# DIDV_-_Controle_Corrente_Total.net
KiCad netlist of a schematic drawn in EAGLE
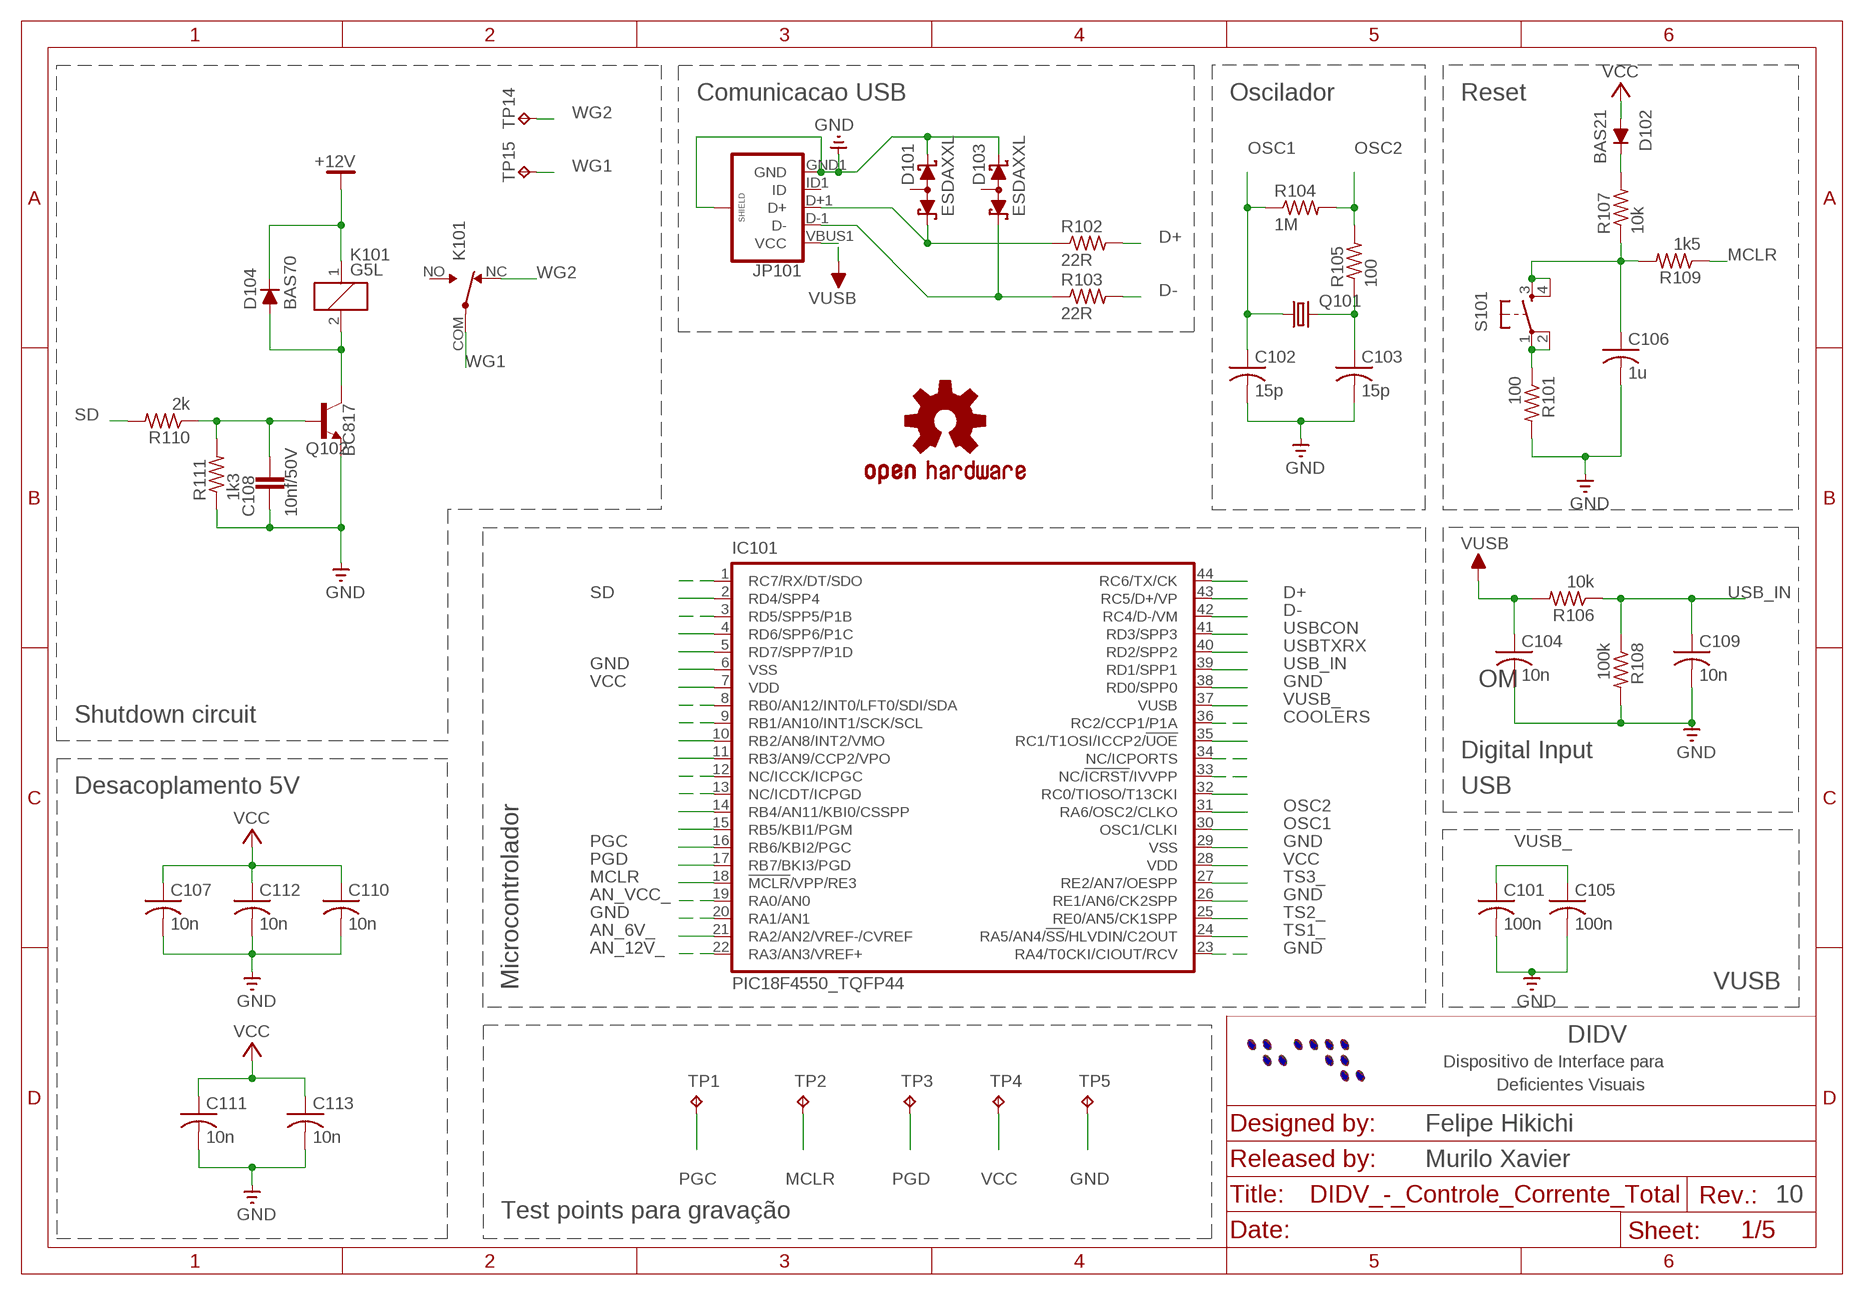
[diagram p0: schematic, sheet 1]
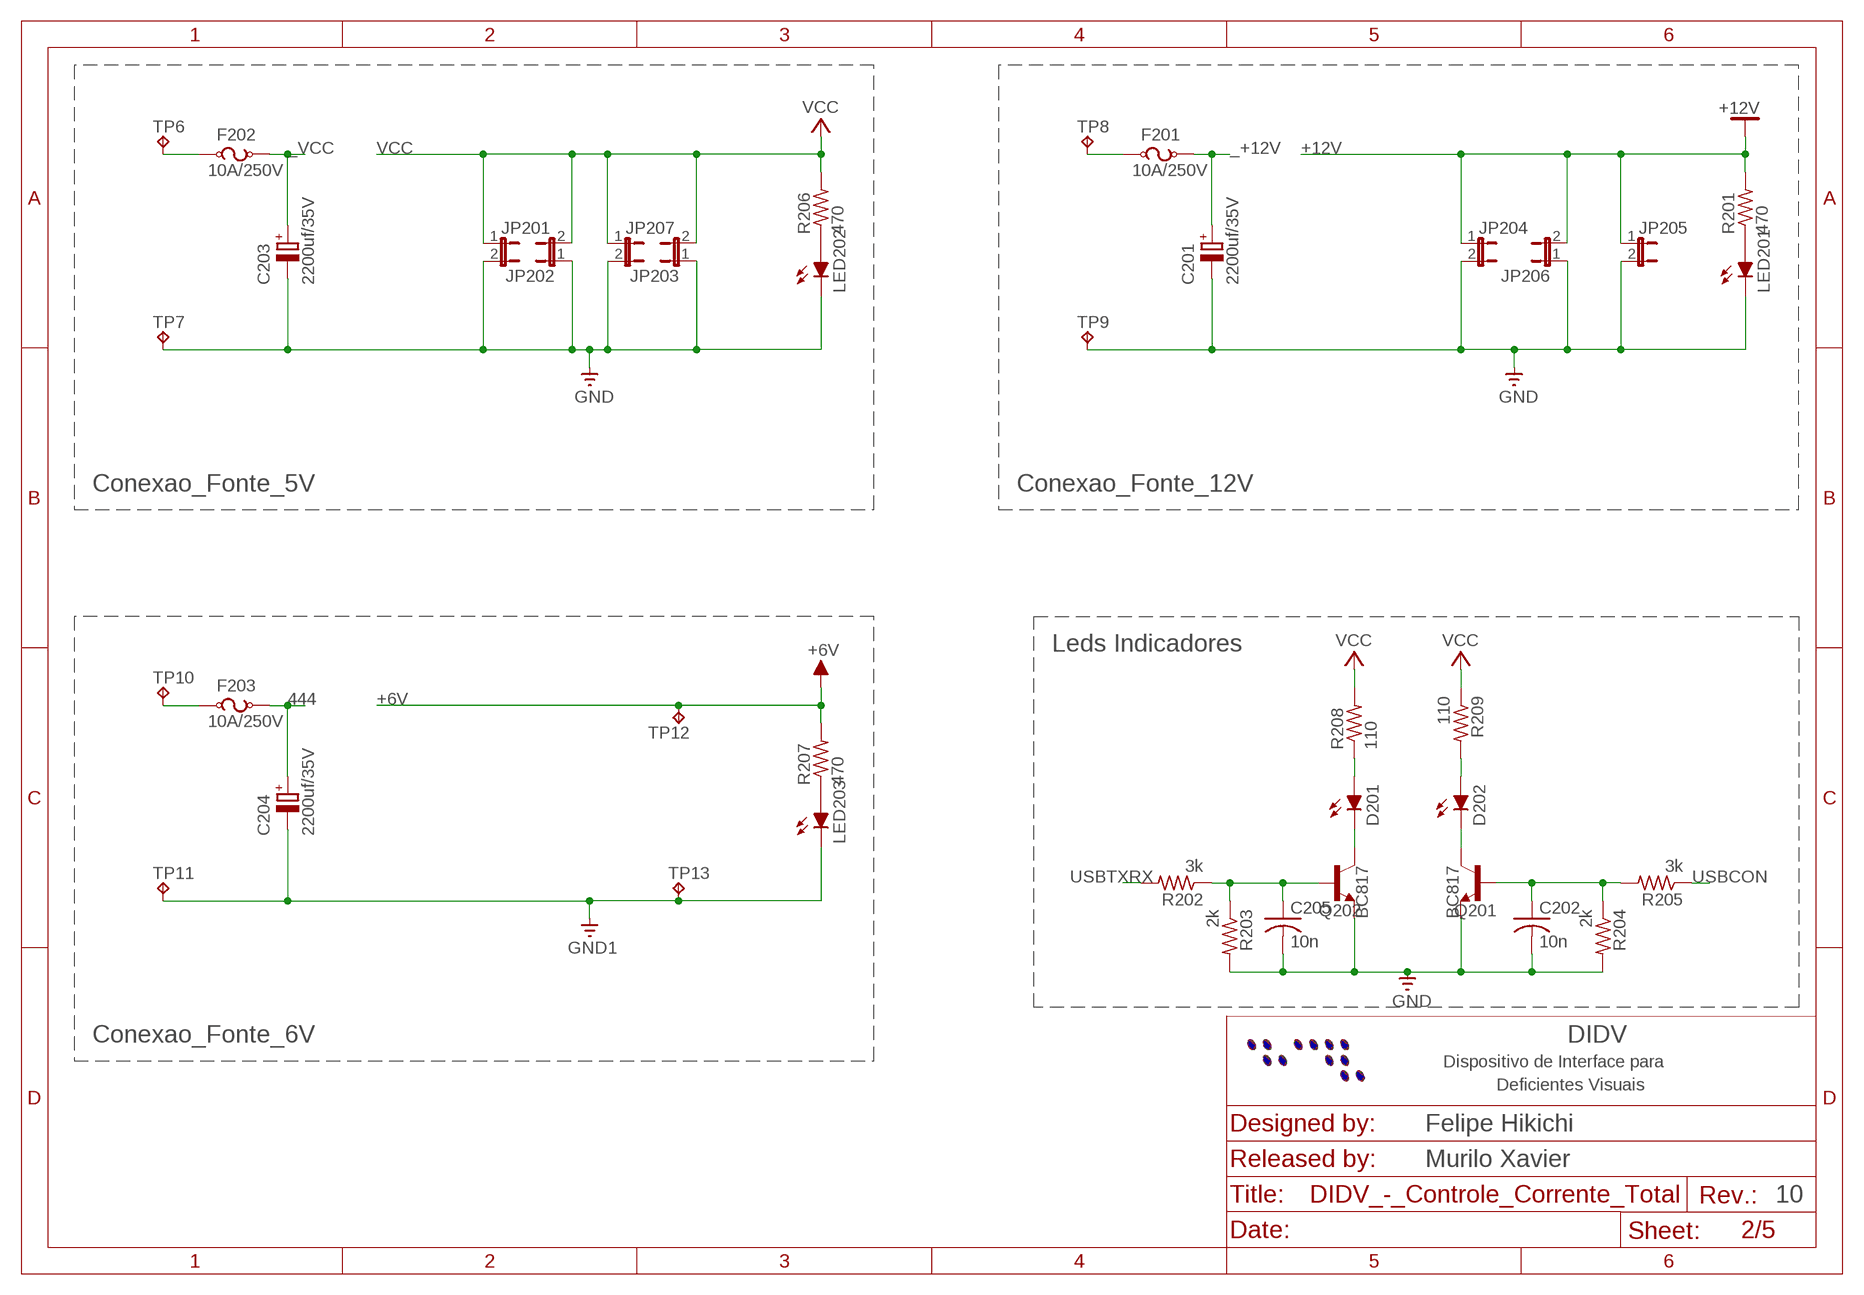
[diagram p1: schematic, sheet 2]
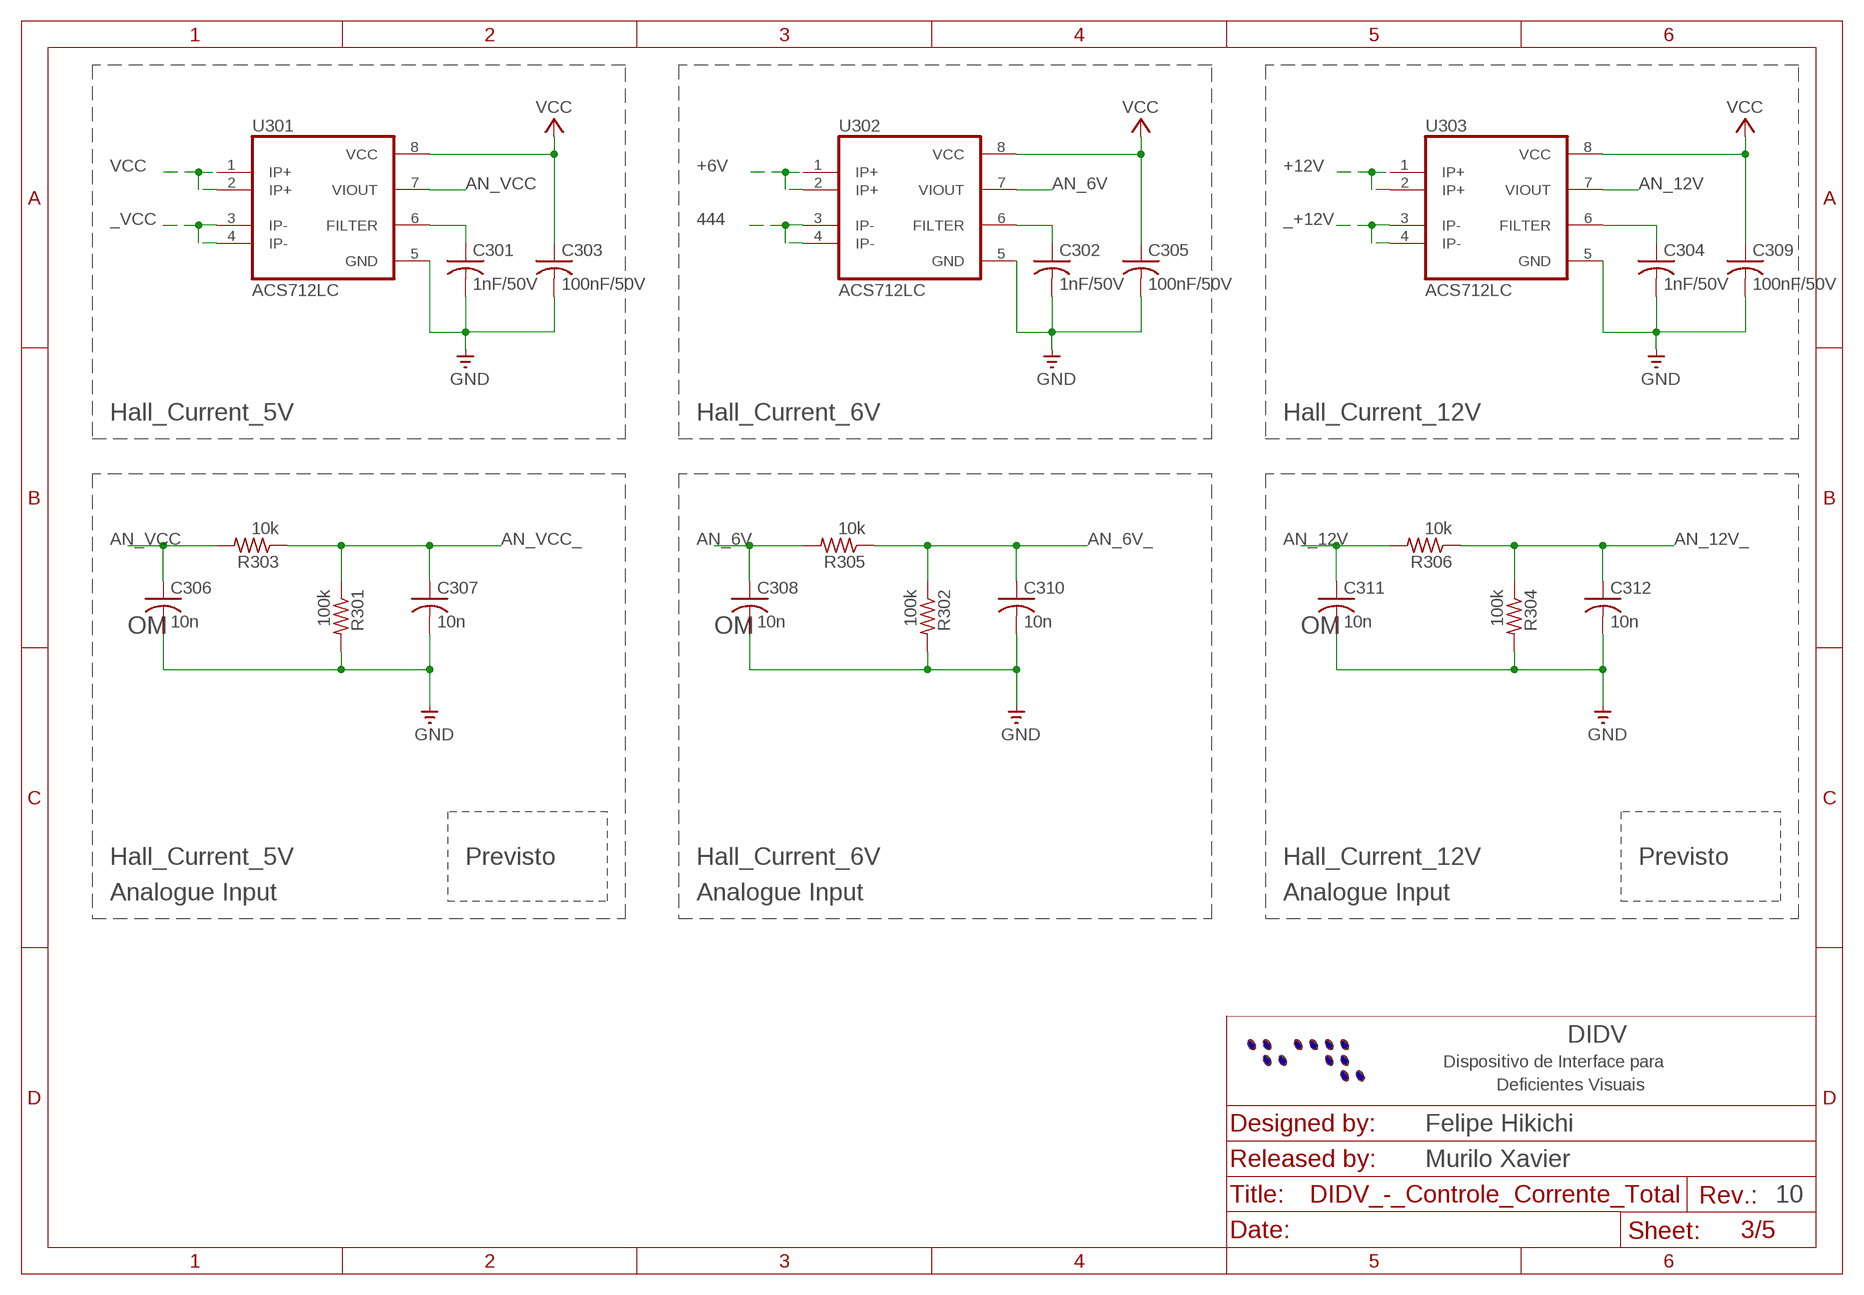
[diagram p2: schematic, sheet 3]
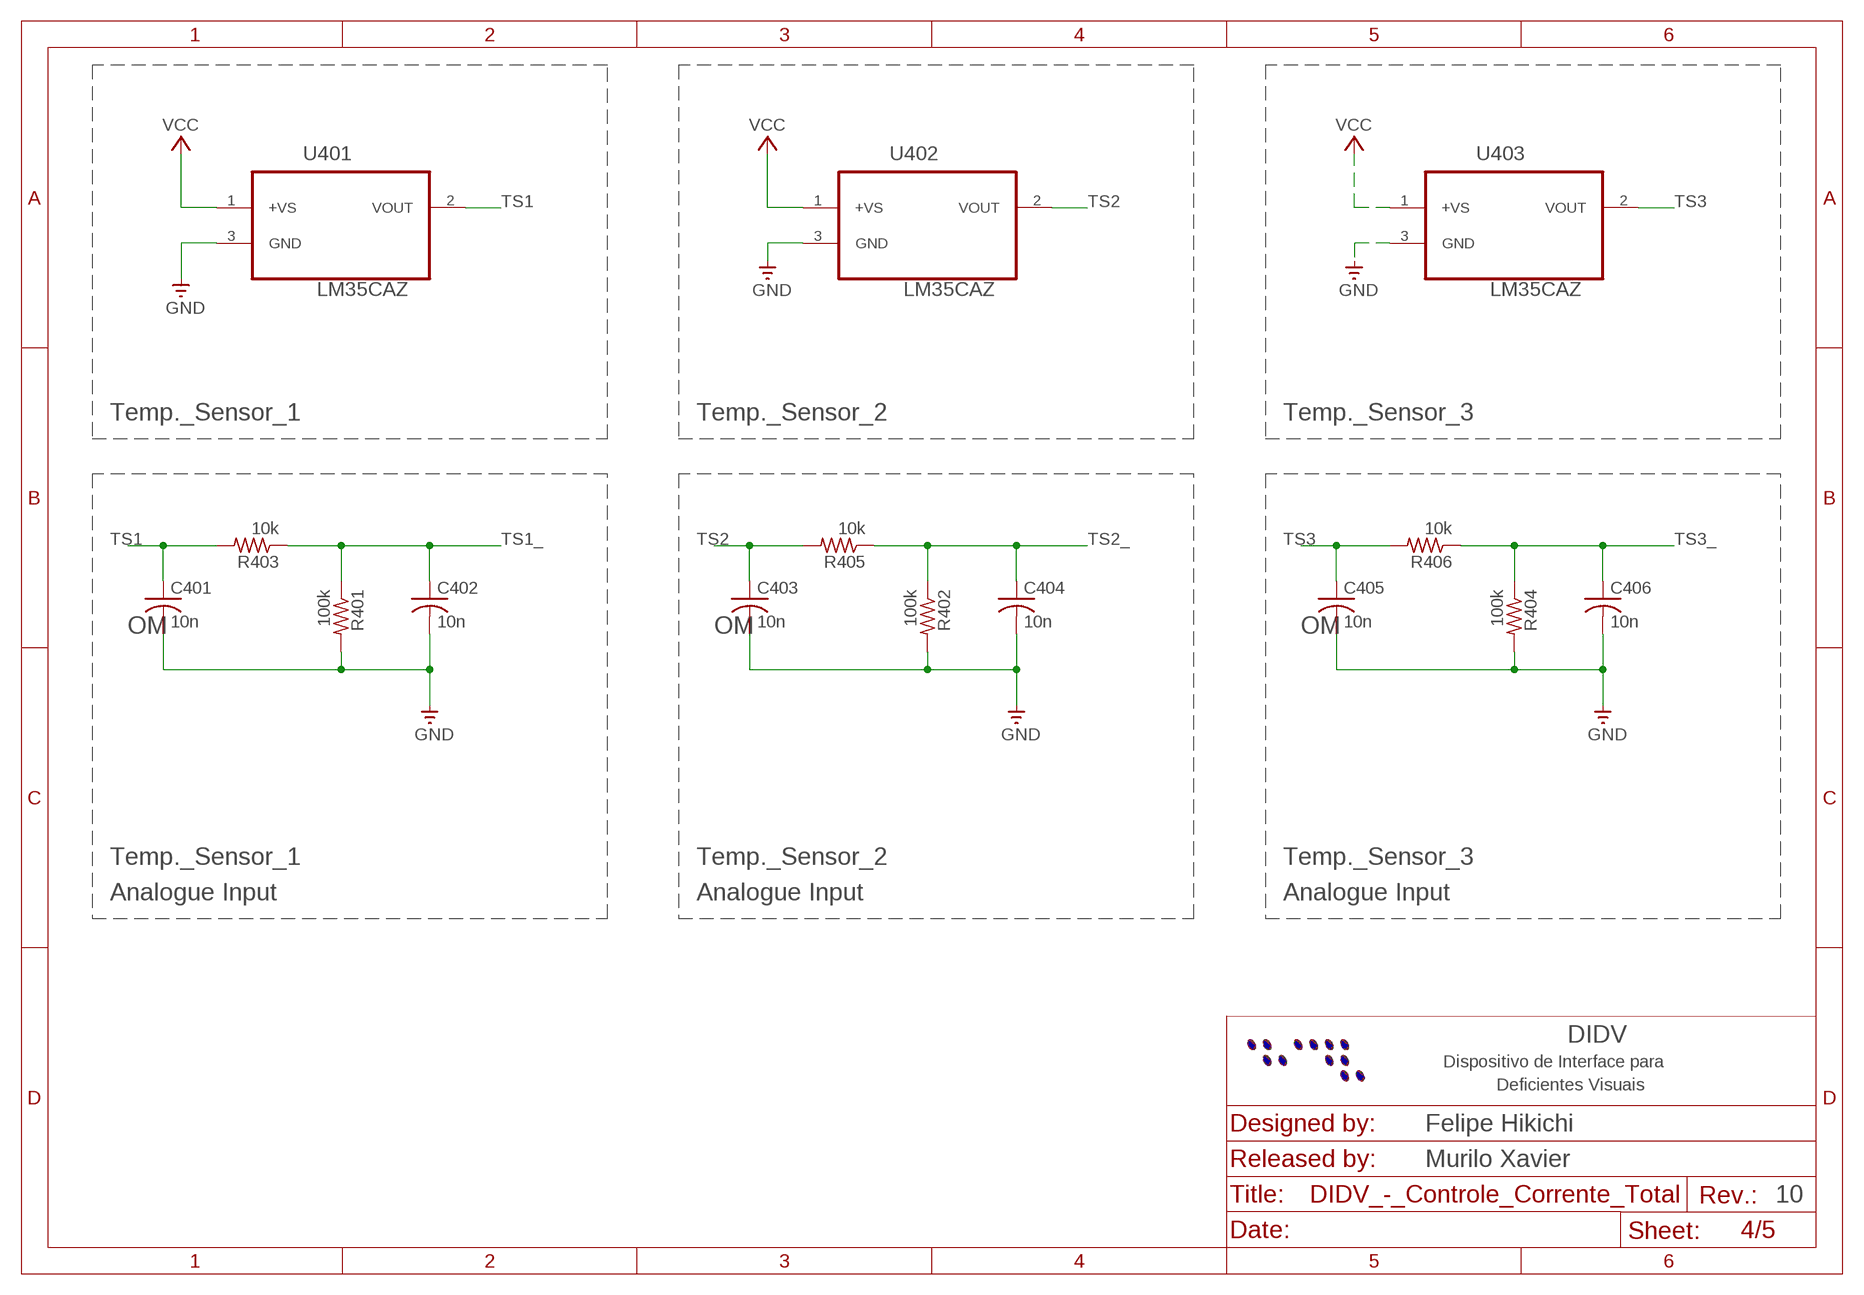
[diagram p3: schematic, sheet 4]
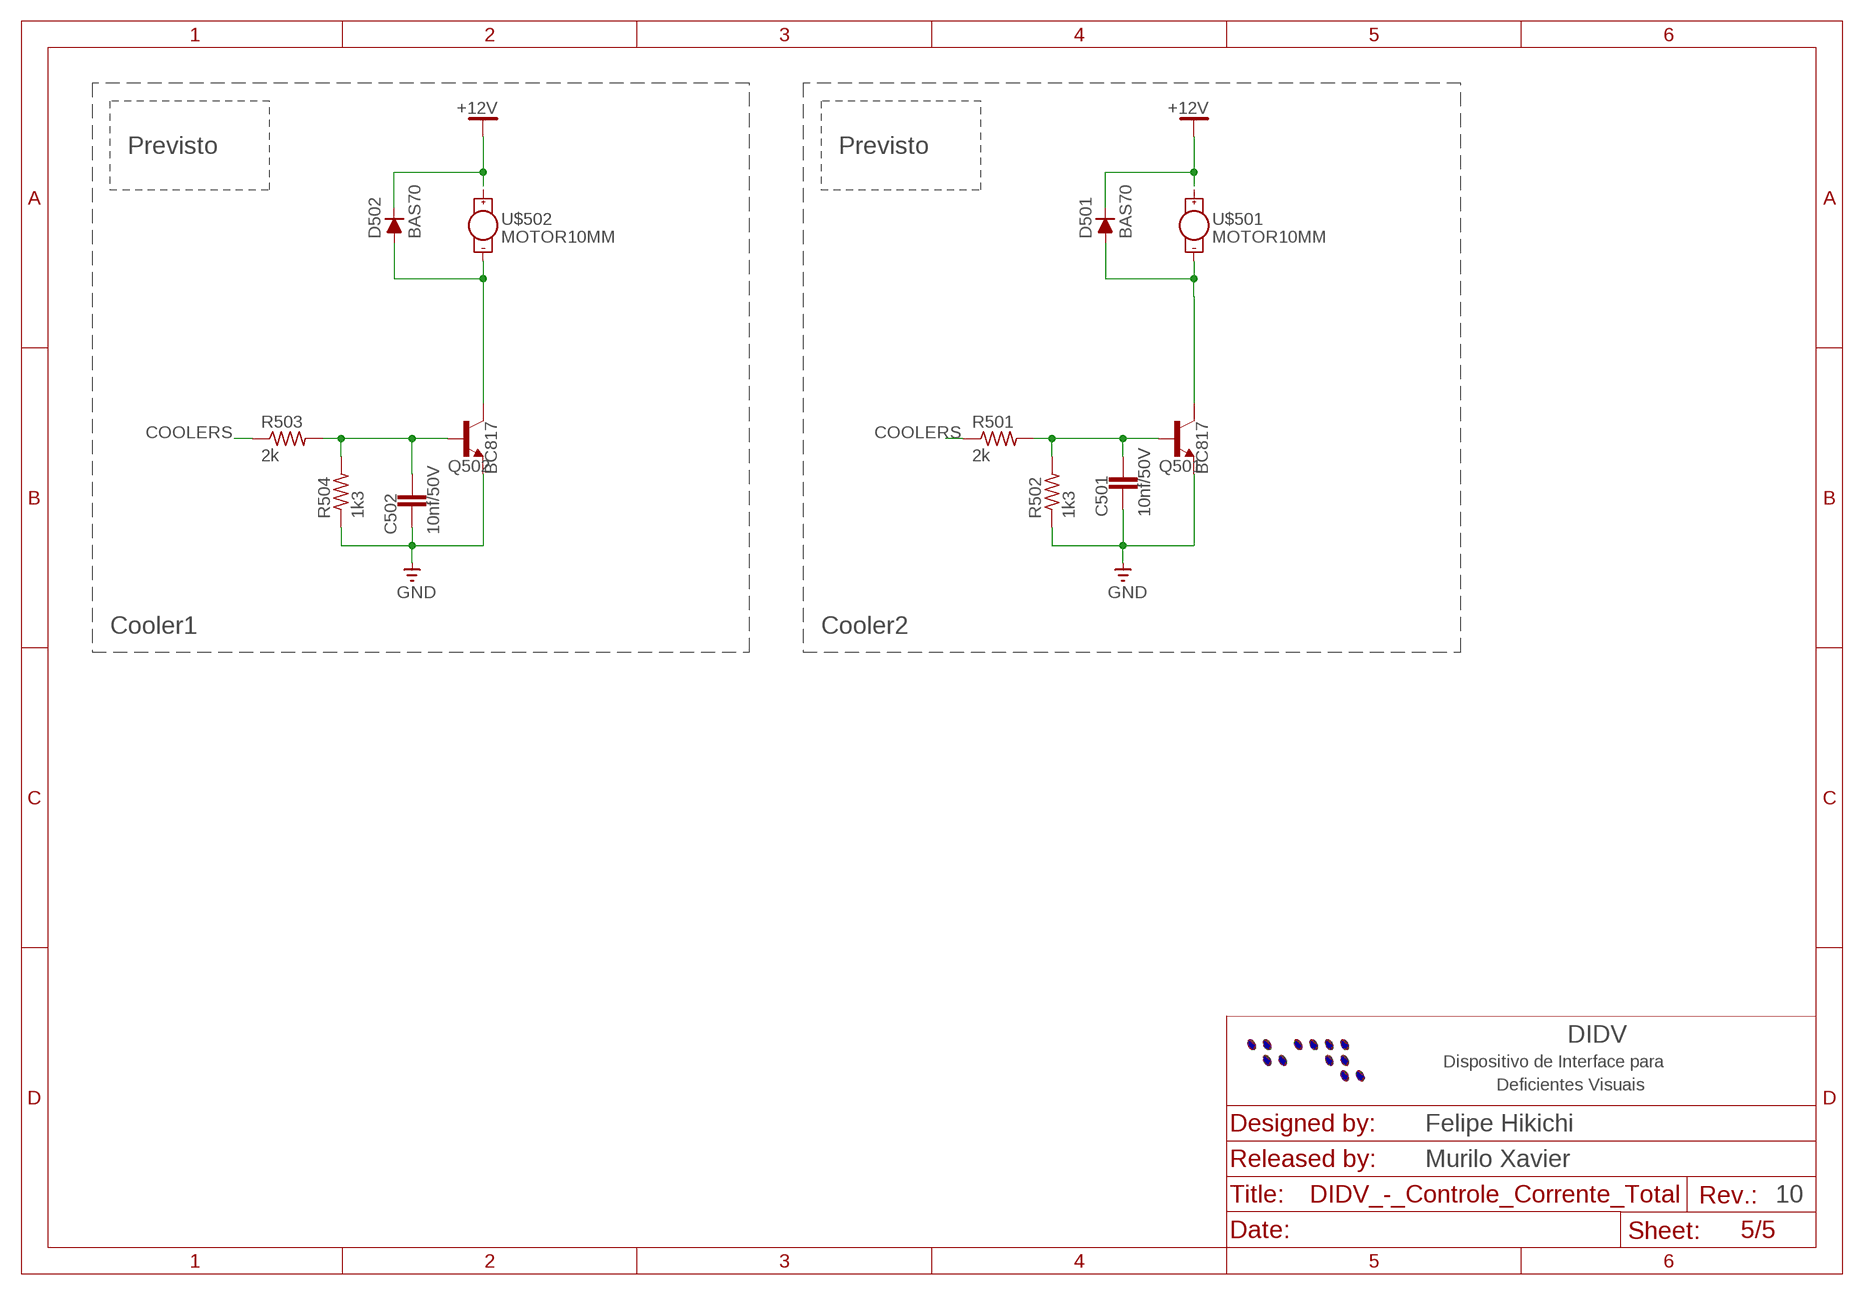
[diagram p4: schematic, sheet 5]

(export (version "E")
  (design (tool "Eeschema 10.0.6"))
  (components
    (comp (ref "C301")
      (value "1nF/50V")
      (footprint "eagle-import:C0603")
      (libsource (lib "eagle-import") (part "C-USC0603"))
    )
    (comp (ref "C302")
      (value "1nF/50V")
      (footprint "eagle-import:C0603")
      (libsource (lib "eagle-import") (part "C-USC0603"))
    )
    (comp (ref "C303")
      (value "100nF/50V")
      (footprint "eagle-import:C0805")
      (libsource (lib "eagle-import") (part "C-USC0805"))
    )
    (comp (ref "C304")
      (value "1nF/50V")
      (footprint "eagle-import:C0603")
      (libsource (lib "eagle-import") (part "C-USC0603"))
    )
    (comp (ref "C305")
      (value "100nF/50V")
      (footprint "eagle-import:C0805")
      (libsource (lib "eagle-import") (part "C-USC0805"))
    )
    (comp (ref "C306")
      (value "10n")
      (footprint "eagle-import:C0805K")
      (libsource (lib "eagle-import") (part "C-USC0805K"))
    )
    (comp (ref "C307")
      (value "10n")
      (footprint "eagle-import:C0603K")
      (libsource (lib "eagle-import") (part "C-USC0603K"))
    )
    (comp (ref "C308")
      (value "10n")
      (footprint "eagle-import:C0805K")
      (libsource (lib "eagle-import") (part "C-USC0805K"))
    )
    (comp (ref "C309")
      (value "100nF/50V")
      (footprint "eagle-import:C0805")
      (libsource (lib "eagle-import") (part "C-USC0805"))
    )
    (comp (ref "C310")
      (value "10n")
      (footprint "eagle-import:C0603K")
      (libsource (lib "eagle-import") (part "C-USC0603K"))
    )
    (comp (ref "C311")
      (value "10n")
      (footprint "eagle-import:C0805K")
      (libsource (lib "eagle-import") (part "C-USC0805K"))
    )
    (comp (ref "C312")
      (value "10n")
      (footprint "eagle-import:C0603K")
      (libsource (lib "eagle-import") (part "C-USC0603K"))
    )
    (comp (ref "R301")
      (value "100k")
      (footprint "eagle-import:R0603")
      (libsource (lib "eagle-import") (part "R-US_R0603"))
    )
    (comp (ref "R302")
      (value "100k")
      (footprint "eagle-import:R0603")
      (libsource (lib "eagle-import") (part "R-US_R0603"))
    )
    (comp (ref "R303")
      (value "10k")
      (footprint "eagle-import:R0603")
      (libsource (lib "eagle-import") (part "R-US_R0603"))
    )
    (comp (ref "R304")
      (value "100k")
      (footprint "eagle-import:R0603")
      (libsource (lib "eagle-import") (part "R-US_R0603"))
    )
    (comp (ref "R305")
      (value "10k")
      (footprint "eagle-import:R0603")
      (libsource (lib "eagle-import") (part "R-US_R0603"))
    )
    (comp (ref "R306")
      (value "10k")
      (footprint "eagle-import:R0603")
      (libsource (lib "eagle-import") (part "R-US_R0603"))
    )
    (comp (ref "U301")
      (value "ACS712LC")
      (footprint "eagle-import:SO08")
      (libsource (lib "eagle-import") (part "ACS712LC"))
    )
    (comp (ref "U302")
      (value "ACS712LC")
      (footprint "eagle-import:SO08")
      (libsource (lib "eagle-import") (part "ACS712LC"))
    )
    (comp (ref "U303")
      (value "ACS712LC")
      (footprint "eagle-import:SO08")
      (libsource (lib "eagle-import") (part "ACS712LC"))
    )
    (comp (ref "C401")
      (value "10n")
      (footprint "eagle-import:C0805K")
      (libsource (lib "eagle-import") (part "C-USC0805K"))
    )
    (comp (ref "C402")
      (value "10n")
      (footprint "eagle-import:C0603K")
      (libsource (lib "eagle-import") (part "C-USC0603K"))
    )
    (comp (ref "C403")
      (value "10n")
      (footprint "eagle-import:C0805K")
      (libsource (lib "eagle-import") (part "C-USC0805K"))
    )
    (comp (ref "C404")
      (value "10n")
      (footprint "eagle-import:C0603K")
      (libsource (lib "eagle-import") (part "C-USC0603K"))
    )
    (comp (ref "C405")
      (value "10n")
      (footprint "eagle-import:C0805K")
      (libsource (lib "eagle-import") (part "C-USC0805K"))
    )
    (comp (ref "C406")
      (value "10n")
      (footprint "eagle-import:C0603K")
      (libsource (lib "eagle-import") (part "C-USC0603K"))
    )
    (comp (ref "R401")
      (value "100k")
      (footprint "eagle-import:R0603")
      (libsource (lib "eagle-import") (part "R-US_R0603"))
    )
    (comp (ref "R402")
      (value "100k")
      (footprint "eagle-import:R0603")
      (libsource (lib "eagle-import") (part "R-US_R0603"))
    )
    (comp (ref "R403")
      (value "10k")
      (footprint "eagle-import:R0603")
      (libsource (lib "eagle-import") (part "R-US_R0603"))
    )
    (comp (ref "R404")
      (value "100k")
      (footprint "eagle-import:R0603")
      (libsource (lib "eagle-import") (part "R-US_R0603"))
    )
    (comp (ref "R405")
      (value "10k")
      (footprint "eagle-import:R0603")
      (libsource (lib "eagle-import") (part "R-US_R0603"))
    )
    (comp (ref "R406")
      (value "10k")
      (footprint "eagle-import:R0603")
      (libsource (lib "eagle-import") (part "R-US_R0603"))
    )
    (comp (ref "U401")
      (value "LM35CAZ")
      (footprint "eagle-import:TO127P254X495-3P")
      (libsource (lib "eagle-import") (part "LM35CAZ"))
    )
    (comp (ref "U402")
      (value "LM35CAZ")
      (footprint "eagle-import:TO127P254X495-3P")
      (libsource (lib "eagle-import") (part "LM35CAZ"))
    )
    (comp (ref "U403")
      (value "LM35CAZ")
      (footprint "eagle-import:TO127P254X495-3P")
      (libsource (lib "eagle-import") (part "LM35CAZ"))
    )
    (comp (ref "C501")
      (value "10nf/50V")
      (footprint "eagle-import:C0603K")
      (libsource (lib "eagle-import") (part "C-EUC0603K"))
    )
    (comp (ref "C502")
      (value "10nf/50V")
      (footprint "eagle-import:C0603K")
      (libsource (lib "eagle-import") (part "C-EUC0603K"))
    )
    (comp (ref "D501")
      (value "BAS70")
      (footprint "eagle-import:SOT23")
      (libsource (lib "eagle-import") (part "BAS40"))
    )
    (comp (ref "D502")
      (value "BAS70")
      (footprint "eagle-import:SOT23")
      (libsource (lib "eagle-import") (part "BAS40"))
    )
    (comp (ref "Q501")
      (value "BC817")
      (footprint "eagle-import:SOT23-BEC")
      (libsource (lib "eagle-import") (part "BC817SMD-16LT1"))
    )
    (comp (ref "Q502")
      (value "BC817")
      (footprint "eagle-import:SOT23-BEC")
      (libsource (lib "eagle-import") (part "BC817SMD-16LT1"))
    )
    (comp (ref "R501")
      (value "2k")
      (footprint "eagle-import:R0603")
      (libsource (lib "eagle-import") (part "R-US_R0603"))
    )
    (comp (ref "R502")
      (value "1k3")
      (footprint "eagle-import:R0603")
      (libsource (lib "eagle-import") (part "R-US_R0603"))
    )
    (comp (ref "R503")
      (value "2k")
      (footprint "eagle-import:R0603")
      (libsource (lib "eagle-import") (part "R-US_R0603"))
    )
    (comp (ref "R504")
      (value "1k3")
      (footprint "eagle-import:R0603")
      (libsource (lib "eagle-import") (part "R-US_R0603"))
    )
    (comp (ref "U$501")
      (value "MOTOR10MM")
      (footprint "eagle-import:VIBE-MOTOR-10MM")
      (libsource (lib "eagle-import") (part "MOTOR10MM"))
    )
    (comp (ref "U$502")
      (value "MOTOR10MM")
      (footprint "eagle-import:VIBE-MOTOR-10MM")
      (libsource (lib "eagle-import") (part "MOTOR10MM"))
    )
    (comp (ref "C101")
      (value "100n")
      (footprint "eagle-import:C0603")
      (libsource (lib "eagle-import") (part "C-USC0603"))
    )
    (comp (ref "C102")
      (value "15p")
      (footprint "eagle-import:C0603K")
      (libsource (lib "eagle-import") (part "C-USC0603K"))
    )
    (comp (ref "C103")
      (value "15p")
      (footprint "eagle-import:C0603K")
      (libsource (lib "eagle-import") (part "C-USC0603K"))
    )
    (comp (ref "C104")
      (value "10n")
      (footprint "eagle-import:C0805K")
      (libsource (lib "eagle-import") (part "C-USC0805K"))
    )
    (comp (ref "C105")
      (value "100n")
      (footprint "eagle-import:C0603")
      (libsource (lib "eagle-import") (part "C-USC0603"))
    )
    (comp (ref "C106")
      (value "1u")
      (footprint "eagle-import:C0805K")
      (libsource (lib "eagle-import") (part "C-USC0805K"))
    )
    (comp (ref "C107")
      (value "10n")
      (footprint "eagle-import:C0603")
      (libsource (lib "eagle-import") (part "C-USC0603"))
    )
    (comp (ref "C108")
      (value "10nf/50V")
      (footprint "eagle-import:C0603K")
      (libsource (lib "eagle-import") (part "C-EUC0603K"))
    )
    (comp (ref "C109")
      (value "10n")
      (footprint "eagle-import:C0603K")
      (libsource (lib "eagle-import") (part "C-USC0603K"))
    )
    (comp (ref "C110")
      (value "10n")
      (footprint "eagle-import:C0805K")
      (libsource (lib "eagle-import") (part "C-USC0805K"))
    )
    (comp (ref "C111")
      (value "10n")
      (footprint "eagle-import:C0805K")
      (libsource (lib "eagle-import") (part "C-USC0805K"))
    )
    (comp (ref "C112")
      (value "10n")
      (footprint "eagle-import:C0603")
      (libsource (lib "eagle-import") (part "C-USC0603"))
    )
    (comp (ref "C113")
      (value "10n")
      (footprint "eagle-import:C0805K")
      (libsource (lib "eagle-import") (part "C-USC0805K"))
    )
    (comp (ref "D101")
      (value "ESDAXXL")
      (footprint "eagle-import:SOT23")
      (libsource (lib "eagle-import") (part "ESDAXXL"))
    )
    (comp (ref "D102")
      (value "BAS21")
      (footprint "eagle-import:SOT23")
      (libsource (lib "eagle-import") (part "BAS19"))
    )
    (comp (ref "D103")
      (value "ESDAXXL")
      (footprint "eagle-import:SOT23")
      (libsource (lib "eagle-import") (part "ESDAXXL"))
    )
    (comp (ref "D104")
      (value "BAS70")
      (footprint "eagle-import:SOT23")
      (libsource (lib "eagle-import") (part "BAS40"))
    )
    (comp (ref "IC101")
      (value "PIC18F4550_TQFP44")
      (footprint "eagle-import:TQFP44")
      (libsource (lib "eagle-import") (part "PIC18F4_TQFP550"))
    )
    (comp (ref "JP101")
      (value "USB_MICROB_PLUGCONN-11752")
      (footprint "eagle-import:USB-B-MICRO-SMD_V03")
      (libsource (lib "eagle-import") (part "USB_MICROB_PLUGCONN-11752"))
    )
    (comp (ref "K101")
      (value "G5L")
      (footprint "eagle-import:G5LE")
      (libsource (lib "eagle-import") (part "G5L"))
    )
    (comp (ref "LOGO101")
      (value "OSHW-LOGOL")
      (footprint "eagle-import:OSHW-LOGO-L")
      (libsource (lib "eagle-import") (part "OSHW-LOGOL"))
    )
    (comp (ref "Q101")
      (value "CRYSTALSM49")
      (footprint "eagle-import:SM49")
      (fields (field (name "OC_FARNELL") "unknown"))
      (libsource (lib "eagle-import") (part "CRYSTALSM49"))
    )
    (comp (ref "Q102")
      (value "BC817")
      (footprint "eagle-import:SOT23-BEC")
      (libsource (lib "eagle-import") (part "BC817SMD-16LT1"))
    )
    (comp (ref "R101")
      (value "100")
      (footprint "eagle-import:R0603")
      (libsource (lib "eagle-import") (part "R-US_R0603"))
    )
    (comp (ref "R102")
      (value "22R")
      (footprint "eagle-import:R0603")
      (libsource (lib "eagle-import") (part "R-US_R0603"))
    )
    (comp (ref "R103")
      (value "22R")
      (footprint "eagle-import:R0603")
      (libsource (lib "eagle-import") (part "R-US_R0603"))
    )
    (comp (ref "R104")
      (value "1M")
      (footprint "eagle-import:R0603")
      (libsource (lib "eagle-import") (part "R-US_R0603"))
    )
    (comp (ref "R105")
      (value "100")
      (footprint "eagle-import:R0603")
      (libsource (lib "eagle-import") (part "R-US_R0603"))
    )
    (comp (ref "R106")
      (value "10k")
      (footprint "eagle-import:R0603")
      (libsource (lib "eagle-import") (part "R-US_R0603"))
    )
    (comp (ref "R107")
      (value "10k")
      (footprint "eagle-import:R0603")
      (libsource (lib "eagle-import") (part "R-US_R0603"))
    )
    (comp (ref "R108")
      (value "100k")
      (footprint "eagle-import:R0603")
      (libsource (lib "eagle-import") (part "R-US_R0603"))
    )
    (comp (ref "R109")
      (value "1k5")
      (footprint "eagle-import:R0603")
      (libsource (lib "eagle-import") (part "R-US_R0603"))
    )
    (comp (ref "R110")
      (value "2k")
      (footprint "eagle-import:R0603")
      (libsource (lib "eagle-import") (part "R-US_R0603"))
    )
    (comp (ref "R111")
      (value "1k3")
      (footprint "eagle-import:R0603")
      (libsource (lib "eagle-import") (part "R-US_R0603"))
    )
    (comp (ref "S101")
      (value "TAC_SWITCHPTH")
      (footprint "eagle-import:TACTILE-PTH")
      (libsource (lib "eagle-import") (part "TAC_SWITCHPTH"))
    )
    (comp (ref "TP1")
      (value "TPB1,27")
      (footprint "eagle-import:B1,27")
      (libsource (lib "eagle-import") (part "TPB1,27"))
    )
    (comp (ref "TP2")
      (value "TPB1,27")
      (footprint "eagle-import:B1,27")
      (libsource (lib "eagle-import") (part "TPB1,27"))
    )
    (comp (ref "TP3")
      (value "TPB1,27")
      (footprint "eagle-import:B1,27")
      (libsource (lib "eagle-import") (part "TPB1,27"))
    )
    (comp (ref "TP4")
      (value "TPB1,27")
      (footprint "eagle-import:B1,27")
      (libsource (lib "eagle-import") (part "TPB1,27"))
    )
    (comp (ref "TP5")
      (value "TPB1,27")
      (footprint "eagle-import:B1,27")
      (libsource (lib "eagle-import") (part "TPB1,27"))
    )
    (comp (ref "TP14")
      (value "TP-063")
      (footprint "eagle-import:TP-063")
      (libsource (lib "eagle-import") (part "TP-063"))
    )
    (comp (ref "TP15")
      (value "TP-063")
      (footprint "eagle-import:TP-063")
      (libsource (lib "eagle-import") (part "TP-063"))
    )
    (comp (ref "C201")
      (value "2200uf/35V")
      (footprint "eagle-import:E3,5-10")
      (libsource (lib "eagle-import") (part "CPOL-EUE3.5-10"))
    )
    (comp (ref "C202")
      (value "10n")
      (footprint "eagle-import:C0603")
      (libsource (lib "eagle-import") (part "C-USC0603"))
    )
    (comp (ref "C203")
      (value "2200uf/35V")
      (footprint "eagle-import:E3,5-10")
      (libsource (lib "eagle-import") (part "CPOL-EUE3.5-10"))
    )
    (comp (ref "C204")
      (value "2200uf/35V")
      (footprint "eagle-import:E3,5-10")
      (libsource (lib "eagle-import") (part "CPOL-EUE3.5-10"))
    )
    (comp (ref "C205")
      (value "10n")
      (footprint "eagle-import:C0603")
      (libsource (lib "eagle-import") (part "C-USC0603"))
    )
    (comp (ref "D201")
      (value "LEDTOPLED-SANTANA")
      (footprint "eagle-import:MINI-TOPLED-SANTANA")
      (libsource (lib "eagle-import") (part "LEDTOPLED-SANTANA"))
    )
    (comp (ref "D202")
      (value "LEDTOPLED-SANTANA")
      (footprint "eagle-import:MINI-TOPLED-SANTANA")
      (libsource (lib "eagle-import") (part "LEDTOPLED-SANTANA"))
    )
    (comp (ref "F201")
      (value "10A/250V")
      (footprint "eagle-import:KS9V")
      (libsource (lib "eagle-import") (part "KS9V"))
    )
    (comp (ref "F202")
      (value "10A/250V")
      (footprint "eagle-import:KS9V")
      (libsource (lib "eagle-import") (part "KS9V"))
    )
    (comp (ref "F203")
      (value "10A/250V")
      (footprint "eagle-import:KS9V")
      (libsource (lib "eagle-import") (part "KS9V"))
    )
    (comp (ref "JP201")
      (value "JP1EY")
      (footprint "eagle-import:JP1Y")
      (libsource (lib "eagle-import") (part "JP1EY"))
    )
    (comp (ref "JP202")
      (value "JP1EY")
      (footprint "eagle-import:JP1Y")
      (libsource (lib "eagle-import") (part "JP1EY"))
    )
    (comp (ref "JP203")
      (value "JP1EY")
      (footprint "eagle-import:JP1Y")
      (libsource (lib "eagle-import") (part "JP1EY"))
    )
    (comp (ref "JP204")
      (value "JP1EY")
      (footprint "eagle-import:JP1Y")
      (libsource (lib "eagle-import") (part "JP1EY"))
    )
    (comp (ref "JP205")
      (value "JP1EY")
      (footprint "eagle-import:JP1Y")
      (libsource (lib "eagle-import") (part "JP1EY"))
    )
    (comp (ref "JP206")
      (value "JP1EY")
      (footprint "eagle-import:JP1Y")
      (libsource (lib "eagle-import") (part "JP1EY"))
    )
    (comp (ref "JP207")
      (value "JP1EY")
      (footprint "eagle-import:JP1Y")
      (libsource (lib "eagle-import") (part "JP1EY"))
    )
    (comp (ref "LED201")
      (value "LEDP-LCC-2")
      (footprint "eagle-import:P-LCC-2")
      (libsource (lib "eagle-import") (part "LEDP-LCC-2"))
    )
    (comp (ref "LED202")
      (value "LEDP-LCC-2")
      (footprint "eagle-import:P-LCC-2")
      (libsource (lib "eagle-import") (part "LEDP-LCC-2"))
    )
    (comp (ref "LED203")
      (value "LEDP-LCC-2")
      (footprint "eagle-import:P-LCC-2")
      (libsource (lib "eagle-import") (part "LEDP-LCC-2"))
    )
    (comp (ref "Q201")
      (value "BC817")
      (footprint "eagle-import:SOT23-BEC")
      (libsource (lib "eagle-import") (part "BC817SMD-16LT1"))
    )
    (comp (ref "Q202")
      (value "BC817")
      (footprint "eagle-import:SOT23-BEC")
      (libsource (lib "eagle-import") (part "BC817SMD-16LT1"))
    )
    (comp (ref "R201")
      (value "470")
      (footprint "eagle-import:R1206")
      (libsource (lib "eagle-import") (part "R-US_R1206"))
    )
    (comp (ref "R202")
      (value "3k")
      (footprint "eagle-import:R0603")
      (libsource (lib "eagle-import") (part "R-US_R0603"))
    )
    (comp (ref "R203")
      (value "2k")
      (footprint "eagle-import:R0603")
      (libsource (lib "eagle-import") (part "R-US_R0603"))
    )
    (comp (ref "R204")
      (value "2k")
      (footprint "eagle-import:R0603")
      (libsource (lib "eagle-import") (part "R-US_R0603"))
    )
    (comp (ref "R205")
      (value "3k")
      (footprint "eagle-import:R0603")
      (libsource (lib "eagle-import") (part "R-US_R0603"))
    )
    (comp (ref "R206")
      (value "470")
      (footprint "eagle-import:R1206")
      (libsource (lib "eagle-import") (part "R-US_R1206"))
    )
    (comp (ref "R207")
      (value "470")
      (footprint "eagle-import:R1206")
      (libsource (lib "eagle-import") (part "R-US_R1206"))
    )
    (comp (ref "R208")
      (value "110")
      (footprint "eagle-import:R1206")
      (libsource (lib "eagle-import") (part "R-US_R1206"))
    )
    (comp (ref "R209")
      (value "110")
      (footprint "eagle-import:R1206")
      (libsource (lib "eagle-import") (part "R-US_R1206"))
    )
    (comp (ref "TP6")
      (value "TP-063")
      (footprint "eagle-import:TP-063")
      (libsource (lib "eagle-import") (part "TP-063"))
    )
    (comp (ref "TP7")
      (value "TP-063")
      (footprint "eagle-import:TP-063")
      (libsource (lib "eagle-import") (part "TP-063"))
    )
    (comp (ref "TP8")
      (value "TP-063")
      (footprint "eagle-import:TP-063")
      (libsource (lib "eagle-import") (part "TP-063"))
    )
    (comp (ref "TP9")
      (value "TP-063")
      (footprint "eagle-import:TP-063")
      (libsource (lib "eagle-import") (part "TP-063"))
    )
    (comp (ref "TP10")
      (value "TP-063")
      (footprint "eagle-import:TP-063")
      (libsource (lib "eagle-import") (part "keystone_Gordo_TP-063"))
    )
    (comp (ref "TP11")
      (value "TP-063")
      (footprint "eagle-import:TP-063")
      (libsource (lib "eagle-import") (part "keystone_Gordo_TP-063"))
    )
    (comp (ref "TP12")
      (value "TP-063")
      (footprint "eagle-import:TP-063")
      (libsource (lib "eagle-import") (part "TP-063"))
    )
    (comp (ref "TP13")
      (value "TP-063")
      (footprint "eagle-import:TP-063")
      (libsource (lib "eagle-import") (part "TP-063"))
    )
  )
  (nets
    (net (code "1") (name "+6V") (class "Default")
      (node (ref "R207") (pin "2") (pinfunction "2_2") (pintype "passive"))
      (node (ref "TP12") (pin "1") (pinfunction "1_1") (pintype "passive"))
      (node (ref "U302") (pin "1") (pinfunction "IP+_1") (pintype "passive"))
      (node (ref "U302") (pin "2") (pinfunction "IP+_2") (pintype "passive"))
    )
    (net (code "2") (name "+12V") (class "Default")
      (node (ref "D104") (pin "3") (pinfunction "C_3") (pintype "passive"))
      (node (ref "D501") (pin "3") (pinfunction "C_3") (pintype "passive"))
      (node (ref "D502") (pin "3") (pinfunction "C_3") (pintype "passive"))
      (node (ref "JP204") (pin "1") (pinfunction "1_1") (pintype "passive"))
      (node (ref "JP205") (pin "1") (pinfunction "1_1") (pintype "passive"))
      (node (ref "JP206") (pin "2") (pinfunction "2_2") (pintype "passive"))
      (node (ref "K101") (pin "1") (pinfunction "1_1") (pintype "passive"))
      (node (ref "R201") (pin "2") (pinfunction "2_2") (pintype "passive"))
      (node (ref "U$501") (pin "+") (pinfunction "+_+") (pintype "bidirectional"))
      (node (ref "U$502") (pin "+") (pinfunction "+_+") (pintype "bidirectional"))
      (node (ref "U303") (pin "1") (pinfunction "IP+_1") (pintype "passive"))
      (node (ref "U303") (pin "2") (pinfunction "IP+_2") (pintype "passive"))
    )
    (net (code "3") (name "444") (class "Default")
      (node (ref "C204") (pin "+") (pinfunction "+_+") (pintype "passive"))
      (node (ref "F203") (pin "2") (pinfunction "2_2") (pintype "passive"))
      (node (ref "U302") (pin "3") (pinfunction "IP-_3") (pintype "passive"))
      (node (ref "U302") (pin "4") (pinfunction "IP-_4") (pintype "passive"))
    )
    (net (code "4") (name "AN_6V") (class "Default")
      (node (ref "C308") (pin "1") (pinfunction "1_1") (pintype "passive"))
      (node (ref "R305") (pin "2") (pinfunction "2_2") (pintype "passive"))
      (node (ref "U302") (pin "7") (pinfunction "VIOUT_7") (pintype "output"))
    )
    (net (code "5") (name "AN_6V_") (class "Default")
      (node (ref "C310") (pin "1") (pinfunction "1_1") (pintype "passive"))
      (node (ref "IC101") (pin "21") (pinfunction "RA2/AN2/VREF-/CVREF_21") (pintype "bidirectional"))
      (node (ref "R302") (pin "1") (pinfunction "1_1") (pintype "passive"))
      (node (ref "R305") (pin "1") (pinfunction "1_1") (pintype "passive"))
    )
    (net (code "6") (name "AN_12V") (class "Default")
      (node (ref "C311") (pin "1") (pinfunction "1_1") (pintype "passive"))
      (node (ref "R306") (pin "2") (pinfunction "2_2") (pintype "passive"))
      (node (ref "U303") (pin "7") (pinfunction "VIOUT_7") (pintype "output"))
    )
    (net (code "7") (name "AN_12V_") (class "Default")
      (node (ref "C312") (pin "1") (pinfunction "1_1") (pintype "passive"))
      (node (ref "IC101") (pin "22") (pinfunction "RA3/AN3/VREF+_22") (pintype "bidirectional"))
      (node (ref "R304") (pin "1") (pinfunction "1_1") (pintype "passive"))
      (node (ref "R306") (pin "1") (pinfunction "1_1") (pintype "passive"))
    )
    (net (code "8") (name "AN_VCC") (class "Default")
      (node (ref "C306") (pin "1") (pinfunction "1_1") (pintype "passive"))
      (node (ref "R303") (pin "2") (pinfunction "2_2") (pintype "passive"))
      (node (ref "U301") (pin "7") (pinfunction "VIOUT_7") (pintype "output"))
    )
    (net (code "9") (name "AN_VCC_") (class "Default")
      (node (ref "C307") (pin "1") (pinfunction "1_1") (pintype "passive"))
      (node (ref "IC101") (pin "19") (pinfunction "RA0/AN0_19") (pintype "bidirectional"))
      (node (ref "R301") (pin "1") (pinfunction "1_1") (pintype "passive"))
      (node (ref "R303") (pin "1") (pinfunction "1_1") (pintype "passive"))
    )
    (net (code "10") (name "COOLERS") (class "Default")
      (node (ref "IC101") (pin "36") (pinfunction "RC2/CCP1/P1A_36") (pintype "bidirectional"))
      (node (ref "R501") (pin "1") (pinfunction "1_1") (pintype "passive"))
      (node (ref "R503") (pin "1") (pinfunction "1_1") (pintype "passive"))
    )
    (net (code "11") (name "D+") (class "Default")
      (node (ref "IC101") (pin "43") (pinfunction "RC5/D+/VP_43") (pintype "bidirectional"))
      (node (ref "R102") (pin "2") (pinfunction "2_2") (pintype "passive"))
    )
    (net (code "12") (name "D-") (class "Default")
      (node (ref "IC101") (pin "42") (pinfunction "RC4/D-/VM_42") (pintype "bidirectional"))
      (node (ref "R103") (pin "2") (pinfunction "2_2") (pintype "passive"))
    )
    (net (code "13") (name "GND") (class "Default")
      (node (ref "C101") (pin "2") (pinfunction "2_2") (pintype "passive"))
      (node (ref "C102") (pin "2") (pinfunction "2_2") (pintype "passive"))
      (node (ref "C103") (pin "2") (pinfunction "2_2") (pintype "passive"))
      (node (ref "C104") (pin "2") (pinfunction "2_2") (pintype "passive"))
      (node (ref "C105") (pin "2") (pinfunction "2_2") (pintype "passive"))
      (node (ref "C106") (pin "2") (pinfunction "2_2") (pintype "passive"))
      (node (ref "C107") (pin "2") (pinfunction "2_2") (pintype "passive"))
      (node (ref "C108") (pin "2") (pinfunction "2_2") (pintype "passive"))
      (node (ref "C109") (pin "2") (pinfunction "2_2") (pintype "passive"))
      (node (ref "C110") (pin "2") (pinfunction "2_2") (pintype "passive"))
      (node (ref "C111") (pin "2") (pinfunction "2_2") (pintype "passive"))
      (node (ref "C112") (pin "2") (pinfunction "2_2") (pintype "passive"))
      (node (ref "C113") (pin "2") (pinfunction "2_2") (pintype "passive"))
      (node (ref "C201") (pin "-") (pinfunction "-_-") (pintype "passive"))
      (node (ref "C202") (pin "2") (pinfunction "2_2") (pintype "passive"))
      (node (ref "C203") (pin "-") (pinfunction "-_-") (pintype "passive"))
      (node (ref "C205") (pin "2") (pinfunction "2_2") (pintype "passive"))
      (node (ref "C301") (pin "2") (pinfunction "2_2") (pintype "passive"))
      (node (ref "C302") (pin "2") (pinfunction "2_2") (pintype "passive"))
      (node (ref "C303") (pin "2") (pinfunction "2_2") (pintype "passive"))
      (node (ref "C304") (pin "2") (pinfunction "2_2") (pintype "passive"))
      (node (ref "C305") (pin "2") (pinfunction "2_2") (pintype "passive"))
      (node (ref "C306") (pin "2") (pinfunction "2_2") (pintype "passive"))
      (node (ref "C307") (pin "2") (pinfunction "2_2") (pintype "passive"))
      (node (ref "C308") (pin "2") (pinfunction "2_2") (pintype "passive"))
      (node (ref "C309") (pin "2") (pinfunction "2_2") (pintype "passive"))
      (node (ref "C310") (pin "2") (pinfunction "2_2") (pintype "passive"))
      (node (ref "C311") (pin "2") (pinfunction "2_2") (pintype "passive"))
      (node (ref "C312") (pin "2") (pinfunction "2_2") (pintype "passive"))
      (node (ref "C401") (pin "2") (pinfunction "2_2") (pintype "passive"))
      (node (ref "C402") (pin "2") (pinfunction "2_2") (pintype "passive"))
      (node (ref "C403") (pin "2") (pinfunction "2_2") (pintype "passive"))
      (node (ref "C404") (pin "2") (pinfunction "2_2") (pintype "passive"))
      (node (ref "C405") (pin "2") (pinfunction "2_2") (pintype "passive"))
      (node (ref "C406") (pin "2") (pinfunction "2_2") (pintype "passive"))
      (node (ref "C501") (pin "2") (pinfunction "2_2") (pintype "passive"))
      (node (ref "C502") (pin "2") (pinfunction "2_2") (pintype "passive"))
      (node (ref "D101") (pin "2") (pinfunction "C2_2") (pintype "passive"))
      (node (ref "D103") (pin "2") (pinfunction "C2_2") (pintype "passive"))
      (node (ref "IC101") (pin "20") (pinfunction "RA1/AN1_20") (pintype "bidirectional"))
      (node (ref "IC101") (pin "23") (pinfunction "RA4/T0CKI/CIOUT/RCV_23") (pintype "bidirectional"))
      (node (ref "IC101") (pin "26") (pinfunction "RE1/AN6/CK2SPP_26") (pintype "bidirectional"))
      (node (ref "IC101") (pin "29") (pinfunction "VSS_29") (pintype "power_in"))
      (node (ref "IC101") (pin "38") (pinfunction "RD0/SPP0_38") (pintype "bidirectional"))
      (node (ref "IC101") (pin "6") (pinfunction "VSS_6") (pintype "power_in"))
      (node (ref "JP101") (pin "GND1") (pinfunction "GND_GND1") (pintype "bidirectional"))
      (node (ref "JP101") (pin "SHIELD1") (pinfunction "SHIELD_SHIELD1") (pintype "bidirectional"))
      (node (ref "JP101") (pin "SHIELD2") (pinfunction "SHIELD_SHIELD2") (pintype "bidirectional"))
      (node (ref "JP101") (pin "SHIELD3") (pinfunction "SHIELD_SHIELD3") (pintype "bidirectional"))
      (node (ref "JP201") (pin "2") (pinfunction "2_2") (pintype "passive"))
      (node (ref "JP202") (pin "1") (pinfunction "1_1") (pintype "passive"))
      (node (ref "JP203") (pin "1") (pinfunction "1_1") (pintype "passive"))
      (node (ref "JP204") (pin "2") (pinfunction "2_2") (pintype "passive"))
      (node (ref "JP205") (pin "2") (pinfunction "2_2") (pintype "passive"))
      (node (ref "JP206") (pin "1") (pinfunction "1_1") (pintype "passive"))
      (node (ref "JP207") (pin "2") (pinfunction "2_2") (pintype "passive"))
      (node (ref "LED201") (pin "C") (pinfunction "C_C") (pintype "passive"))
      (node (ref "LED202") (pin "C") (pinfunction "C_C") (pintype "passive"))
      (node (ref "Q102") (pin "E") (pinfunction "E_E") (pintype "passive"))
      (node (ref "Q201") (pin "E") (pinfunction "E_E") (pintype "passive"))
      (node (ref "Q202") (pin "E") (pinfunction "E_E") (pintype "passive"))
      (node (ref "Q501") (pin "E") (pinfunction "E_E") (pintype "passive"))
      (node (ref "Q502") (pin "E") (pinfunction "E_E") (pintype "passive"))
      (node (ref "R101") (pin "2") (pinfunction "2_2") (pintype "passive"))
      (node (ref "R108") (pin "2") (pinfunction "2_2") (pintype "passive"))
      (node (ref "R111") (pin "1") (pinfunction "1_1") (pintype "passive"))
      (node (ref "R203") (pin "2") (pinfunction "2_2") (pintype "passive"))
      (node (ref "R204") (pin "2") (pinfunction "2_2") (pintype "passive"))
      (node (ref "R301") (pin "2") (pinfunction "2_2") (pintype "passive"))
      (node (ref "R302") (pin "2") (pinfunction "2_2") (pintype "passive"))
      (node (ref "R304") (pin "2") (pinfunction "2_2") (pintype "passive"))
      (node (ref "R401") (pin "2") (pinfunction "2_2") (pintype "passive"))
      (node (ref "R402") (pin "2") (pinfunction "2_2") (pintype "passive"))
      (node (ref "R404") (pin "2") (pinfunction "2_2") (pintype "passive"))
      (node (ref "R502") (pin "1") (pinfunction "1_1") (pintype "passive"))
      (node (ref "R504") (pin "1") (pinfunction "1_1") (pintype "passive"))
      (node (ref "TP5") (pin "TP") (pinfunction "TP_TP") (pintype "input"))
      (node (ref "TP7") (pin "1") (pinfunction "1_1") (pintype "passive"))
      (node (ref "TP9") (pin "1") (pinfunction "1_1") (pintype "passive"))
      (node (ref "U301") (pin "5") (pinfunction "GND_5") (pintype "power_in"))
      (node (ref "U302") (pin "5") (pinfunction "GND_5") (pintype "power_in"))
      (node (ref "U303") (pin "5") (pinfunction "GND_5") (pintype "power_in"))
      (node (ref "U401") (pin "3") (pinfunction "GND_3") (pintype "passive"))
      (node (ref "U402") (pin "3") (pinfunction "GND_3") (pintype "passive"))
      (node (ref "U403") (pin "3") (pinfunction "GND_3") (pintype "passive"))
    )
    (net (code "14") (name "GND1") (class "Default")
      (node (ref "C204") (pin "-") (pinfunction "-_-") (pintype "passive"))
      (node (ref "LED203") (pin "C") (pinfunction "C_C") (pintype "passive"))
      (node (ref "TP11") (pin "1") (pinfunction "1_1") (pintype "passive"))
      (node (ref "TP13") (pin "1") (pinfunction "1_1") (pintype "passive"))
    )
    (net (code "15") (name "MCLR") (class "Default")
      (node (ref "IC101") (pin "18") (pinfunction "~{MCLR}/VPP/RE3_18") (pintype "input"))
      (node (ref "R109") (pin "1") (pinfunction "1_1") (pintype "passive"))
      (node (ref "TP2") (pin "TP") (pinfunction "TP_TP") (pintype "input"))
    )
    (net (code "16") (name "Net-(C103-Pad1)") (class "Default")
      (node (ref "C103") (pin "1") (pinfunction "1_1") (pintype "passive"))
      (node (ref "Q101") (pin "2") (pinfunction "2_2") (pintype "passive"))
      (node (ref "R105") (pin "1") (pinfunction "1_1") (pintype "passive"))
    )
    (net (code "17") (name "Net-(C106-Pad1)") (class "Default")
      (node (ref "C106") (pin "1") (pinfunction "1_1") (pintype "passive"))
      (node (ref "R107") (pin "1") (pinfunction "1_1") (pintype "passive"))
      (node (ref "R109") (pin "2") (pinfunction "2_2") (pintype "passive"))
      (node (ref "S101") (pin "3") (pinfunction "3_3") (pintype "passive"))
      (node (ref "S101") (pin "4") (pinfunction "4_4") (pintype "passive"))
    )
    (net (code "18") (name "Net-(C108-Pad1)") (class "Default")
      (node (ref "C108") (pin "1") (pinfunction "1_1") (pintype "passive"))
      (node (ref "Q102") (pin "B") (pinfunction "B_B") (pintype "passive"))
      (node (ref "R110") (pin "1") (pinfunction "1_1") (pintype "passive"))
      (node (ref "R111") (pin "2") (pinfunction "2_2") (pintype "passive"))
    )
    (net (code "19") (name "Net-(C202-Pad1)") (class "Default")
      (node (ref "C202") (pin "1") (pinfunction "1_1") (pintype "passive"))
      (node (ref "Q201") (pin "B") (pinfunction "B_B") (pintype "passive"))
      (node (ref "R204") (pin "1") (pinfunction "1_1") (pintype "passive"))
      (node (ref "R205") (pin "2") (pinfunction "2_2") (pintype "passive"))
    )
    (net (code "20") (name "Net-(C205-Pad1)") (class "Default")
      (node (ref "C205") (pin "1") (pinfunction "1_1") (pintype "passive"))
      (node (ref "Q202") (pin "B") (pinfunction "B_B") (pintype "passive"))
      (node (ref "R202") (pin "1") (pinfunction "1_1") (pintype "passive"))
      (node (ref "R203") (pin "1") (pinfunction "1_1") (pintype "passive"))
    )
    (net (code "21") (name "Net-(C501-Pad1)") (class "Default")
      (node (ref "C501") (pin "1") (pinfunction "1_1") (pintype "passive"))
      (node (ref "Q501") (pin "B") (pinfunction "B_B") (pintype "passive"))
      (node (ref "R501") (pin "2") (pinfunction "2_2") (pintype "passive"))
      (node (ref "R502") (pin "2") (pinfunction "2_2") (pintype "passive"))
    )
    (net (code "22") (name "Net-(C502-Pad1)") (class "Default")
      (node (ref "C502") (pin "1") (pinfunction "1_1") (pintype "passive"))
      (node (ref "Q502") (pin "B") (pinfunction "B_B") (pintype "passive"))
      (node (ref "R503") (pin "2") (pinfunction "2_2") (pintype "passive"))
      (node (ref "R504") (pin "2") (pinfunction "2_2") (pintype "passive"))
    )
    (net (code "23") (name "Net-(D101-C1)") (class "Default")
      (node (ref "D101") (pin "1") (pinfunction "C1_1") (pintype "passive"))
      (node (ref "JP101") (pin "D+1") (pinfunction "D+_D+1") (pintype "bidirectional"))
      (node (ref "R102") (pin "1") (pinfunction "1_1") (pintype "passive"))
    )
    (net (code "24") (name "Net-(D102-C)") (class "Default")
      (node (ref "D102") (pin "3") (pinfunction "C_3") (pintype "passive"))
      (node (ref "R107") (pin "2") (pinfunction "2_2") (pintype "passive"))
    )
    (net (code "25") (name "Net-(D103-C1)") (class "Default")
      (node (ref "D103") (pin "1") (pinfunction "C1_1") (pintype "passive"))
      (node (ref "JP101") (pin "D-1") (pinfunction "D-_D-1") (pintype "bidirectional"))
      (node (ref "R103") (pin "1") (pinfunction "1_1") (pintype "passive"))
    )
    (net (code "26") (name "Net-(D104-A)") (class "Default")
      (node (ref "D104") (pin "1") (pinfunction "A_1") (pintype "passive"))
      (node (ref "K101") (pin "2") (pinfunction "2_2") (pintype "passive"))
      (node (ref "Q102") (pin "C") (pinfunction "C_C") (pintype "passive"))
    )
    (net (code "27") (name "Net-(D201-PadA)") (class "Default")
      (node (ref "D201") (pin "A") (pinfunction "A_A") (pintype "passive"))
      (node (ref "R208") (pin "1") (pinfunction "1_1") (pintype "passive"))
    )
    (net (code "28") (name "Net-(D201-PadC)") (class "Default")
      (node (ref "D201") (pin "C") (pinfunction "C_C") (pintype "passive"))
      (node (ref "Q202") (pin "C") (pinfunction "C_C") (pintype "passive"))
    )
    (net (code "29") (name "Net-(D202-PadA)") (class "Default")
      (node (ref "D202") (pin "A") (pinfunction "A_A") (pintype "passive"))
      (node (ref "R209") (pin "2") (pinfunction "2_2") (pintype "passive"))
    )
    (net (code "30") (name "Net-(D202-PadC)") (class "Default")
      (node (ref "D202") (pin "C") (pinfunction "C_C") (pintype "passive"))
      (node (ref "Q201") (pin "C") (pinfunction "C_C") (pintype "passive"))
    )
    (net (code "31") (name "Net-(D501-A)") (class "Default")
      (node (ref "D501") (pin "1") (pinfunction "A_1") (pintype "passive"))
      (node (ref "Q501") (pin "C") (pinfunction "C_C") (pintype "passive"))
      (node (ref "U$501") (pin "-") (pinfunction "-_-") (pintype "bidirectional"))
    )
    (net (code "32") (name "Net-(D502-A)") (class "Default")
      (node (ref "D502") (pin "1") (pinfunction "A_1") (pintype "passive"))
      (node (ref "Q502") (pin "C") (pinfunction "C_C") (pintype "passive"))
      (node (ref "U$502") (pin "-") (pinfunction "-_-") (pintype "bidirectional"))
    )
    (net (code "33") (name "Net-(F201-Pad1)") (class "Default")
      (node (ref "F201") (pin "1") (pinfunction "1_1") (pintype "passive"))
      (node (ref "TP8") (pin "1") (pinfunction "1_1") (pintype "passive"))
    )
    (net (code "34") (name "Net-(F202-Pad1)") (class "Default")
      (node (ref "F202") (pin "1") (pinfunction "1_1") (pintype "passive"))
      (node (ref "TP6") (pin "1") (pinfunction "1_1") (pintype "passive"))
    )
    (net (code "35") (name "Net-(F203-Pad1)") (class "Default")
      (node (ref "F203") (pin "1") (pinfunction "1_1") (pintype "passive"))
      (node (ref "TP10") (pin "1") (pinfunction "1_1") (pintype "passive"))
    )
    (net (code "36") (name "Net-(LED201-PadA)") (class "Default")
      (node (ref "LED201") (pin "A") (pinfunction "A_A") (pintype "passive"))
      (node (ref "R201") (pin "1") (pinfunction "1_1") (pintype "passive"))
    )
    (net (code "37") (name "Net-(LED202-PadA)") (class "Default")
      (node (ref "LED202") (pin "A") (pinfunction "A_A") (pintype "passive"))
      (node (ref "R206") (pin "1") (pinfunction "1_1") (pintype "passive"))
    )
    (net (code "38") (name "Net-(LED203-PadA)") (class "Default")
      (node (ref "LED203") (pin "A") (pinfunction "A_A") (pintype "passive"))
      (node (ref "R207") (pin "1") (pinfunction "1_1") (pintype "passive"))
    )
    (net (code "39") (name "Net-(R101-Pad1)") (class "Default")
      (node (ref "R101") (pin "1") (pinfunction "1_1") (pintype "passive"))
      (node (ref "S101") (pin "1") (pinfunction "1_1") (pintype "passive"))
      (node (ref "S101") (pin "2") (pinfunction "2_2") (pintype "passive"))
    )
    (net (code "40") (name "Net-(U301-FILTER)") (class "Default")
      (node (ref "C301") (pin "1") (pinfunction "1_1") (pintype "passive"))
      (node (ref "U301") (pin "6") (pinfunction "FILTER_6") (pintype "passive"))
    )
    (net (code "41") (name "Net-(U302-FILTER)") (class "Default")
      (node (ref "C302") (pin "1") (pinfunction "1_1") (pintype "passive"))
      (node (ref "U302") (pin "6") (pinfunction "FILTER_6") (pintype "passive"))
    )
    (net (code "42") (name "Net-(U303-FILTER)") (class "Default")
      (node (ref "C304") (pin "1") (pinfunction "1_1") (pintype "passive"))
      (node (ref "U303") (pin "6") (pinfunction "FILTER_6") (pintype "passive"))
    )
    (net (code "43") (name "OSC1") (class "Default")
      (node (ref "C102") (pin "1") (pinfunction "1_1") (pintype "passive"))
      (node (ref "IC101") (pin "30") (pinfunction "OSC1/CLKI_30") (pintype "input"))
      (node (ref "Q101") (pin "1") (pinfunction "1_1") (pintype "passive"))
      (node (ref "R104") (pin "1") (pinfunction "1_1") (pintype "passive"))
    )
    (net (code "44") (name "OSC2") (class "Default")
      (node (ref "IC101") (pin "31") (pinfunction "RA6/OSC2/CLKO_31") (pintype "output"))
      (node (ref "R104") (pin "2") (pinfunction "2_2") (pintype "passive"))
      (node (ref "R105") (pin "2") (pinfunction "2_2") (pintype "passive"))
    )
    (net (code "45") (name "PGC") (class "Default")
      (node (ref "IC101") (pin "16") (pinfunction "RB6/KBI2/PGC_16") (pintype "bidirectional"))
      (node (ref "TP1") (pin "TP") (pinfunction "TP_TP") (pintype "input"))
    )
    (net (code "46") (name "PGD") (class "Default")
      (node (ref "IC101") (pin "17") (pinfunction "RB7/BKI3/PGD_17") (pintype "bidirectional"))
      (node (ref "TP3") (pin "TP") (pinfunction "TP_TP") (pintype "input"))
    )
    (net (code "47") (name "SD") (class "Default")
      (node (ref "IC101") (pin "2") (pinfunction "RD4/SPP4_2") (pintype "bidirectional"))
      (node (ref "R110") (pin "2") (pinfunction "2_2") (pintype "passive"))
    )
    (net (code "48") (name "TS1") (class "Default")
      (node (ref "C401") (pin "1") (pinfunction "1_1") (pintype "passive"))
      (node (ref "R403") (pin "2") (pinfunction "2_2") (pintype "passive"))
      (node (ref "U401") (pin "2") (pinfunction "VOUT_2") (pintype "output"))
    )
    (net (code "49") (name "TS1_") (class "Default")
      (node (ref "C402") (pin "1") (pinfunction "1_1") (pintype "passive"))
      (node (ref "IC101") (pin "24") (pinfunction "RA5/AN4/~{SS}/HLVDIN/C2OUT_24") (pintype "bidirectional"))
      (node (ref "R401") (pin "1") (pinfunction "1_1") (pintype "passive"))
      (node (ref "R403") (pin "1") (pinfunction "1_1") (pintype "passive"))
    )
    (net (code "50") (name "TS2") (class "Default")
      (node (ref "C403") (pin "1") (pinfunction "1_1") (pintype "passive"))
      (node (ref "R405") (pin "2") (pinfunction "2_2") (pintype "passive"))
      (node (ref "U402") (pin "2") (pinfunction "VOUT_2") (pintype "output"))
    )
    (net (code "51") (name "TS2_") (class "Default")
      (node (ref "C404") (pin "1") (pinfunction "1_1") (pintype "passive"))
      (node (ref "IC101") (pin "25") (pinfunction "RE0/AN5/CK1SPP_25") (pintype "bidirectional"))
      (node (ref "R402") (pin "1") (pinfunction "1_1") (pintype "passive"))
      (node (ref "R405") (pin "1") (pinfunction "1_1") (pintype "passive"))
    )
    (net (code "52") (name "TS3") (class "Default")
      (node (ref "C405") (pin "1") (pinfunction "1_1") (pintype "passive"))
      (node (ref "R406") (pin "2") (pinfunction "2_2") (pintype "passive"))
      (node (ref "U403") (pin "2") (pinfunction "VOUT_2") (pintype "output"))
    )
    (net (code "53") (name "TS3_") (class "Default")
      (node (ref "C406") (pin "1") (pinfunction "1_1") (pintype "passive"))
      (node (ref "IC101") (pin "27") (pinfunction "RE2/AN7/OESPP_27") (pintype "bidirectional"))
      (node (ref "R404") (pin "1") (pinfunction "1_1") (pintype "passive"))
      (node (ref "R406") (pin "1") (pinfunction "1_1") (pintype "passive"))
    )
    (net (code "54") (name "USBCON") (class "Default")
      (node (ref "IC101") (pin "41") (pinfunction "RD3/SPP3_41") (pintype "bidirectional"))
      (node (ref "R205") (pin "1") (pinfunction "1_1") (pintype "passive"))
    )
    (net (code "55") (name "USBTXRX") (class "Default")
      (node (ref "IC101") (pin "40") (pinfunction "RD2/SPP2_40") (pintype "bidirectional"))
      (node (ref "R202") (pin "2") (pinfunction "2_2") (pintype "passive"))
    )
    (net (code "56") (name "USB_IN") (class "Default")
      (node (ref "C109") (pin "1") (pinfunction "1_1") (pintype "passive"))
      (node (ref "IC101") (pin "39") (pinfunction "RD1/SPP1_39") (pintype "bidirectional"))
      (node (ref "R106") (pin "1") (pinfunction "1_1") (pintype "passive"))
      (node (ref "R108") (pin "1") (pinfunction "1_1") (pintype "passive"))
    )
    (net (code "57") (name "VCC") (class "Default")
      (node (ref "C107") (pin "1") (pinfunction "1_1") (pintype "passive"))
      (node (ref "C110") (pin "1") (pinfunction "1_1") (pintype "passive"))
      (node (ref "C111") (pin "1") (pinfunction "1_1") (pintype "passive"))
      (node (ref "C112") (pin "1") (pinfunction "1_1") (pintype "passive"))
      (node (ref "C113") (pin "1") (pinfunction "1_1") (pintype "passive"))
      (node (ref "C303") (pin "1") (pinfunction "1_1") (pintype "passive"))
      (node (ref "C305") (pin "1") (pinfunction "1_1") (pintype "passive"))
      (node (ref "C309") (pin "1") (pinfunction "1_1") (pintype "passive"))
      (node (ref "D102") (pin "1") (pinfunction "A_1") (pintype "passive"))
      (node (ref "IC101") (pin "28") (pinfunction "VDD_28") (pintype "power_in"))
      (node (ref "IC101") (pin "7") (pinfunction "VDD_7") (pintype "power_in"))
      (node (ref "JP201") (pin "1") (pinfunction "1_1") (pintype "passive"))
      (node (ref "JP202") (pin "2") (pinfunction "2_2") (pintype "passive"))
      (node (ref "JP203") (pin "2") (pinfunction "2_2") (pintype "passive"))
      (node (ref "JP207") (pin "1") (pinfunction "1_1") (pintype "passive"))
      (node (ref "R206") (pin "2") (pinfunction "2_2") (pintype "passive"))
      (node (ref "R208") (pin "2") (pinfunction "2_2") (pintype "passive"))
      (node (ref "R209") (pin "1") (pinfunction "1_1") (pintype "passive"))
      (node (ref "TP4") (pin "TP") (pinfunction "TP_TP") (pintype "input"))
      (node (ref "U301") (pin "1") (pinfunction "IP+_1") (pintype "passive"))
      (node (ref "U301") (pin "2") (pinfunction "IP+_2") (pintype "passive"))
      (node (ref "U301") (pin "8") (pinfunction "VCC_8") (pintype "power_in"))
      (node (ref "U302") (pin "8") (pinfunction "VCC_8") (pintype "power_in"))
      (node (ref "U303") (pin "8") (pinfunction "VCC_8") (pintype "power_in"))
      (node (ref "U401") (pin "1") (pinfunction "+VS_1") (pintype "power_in"))
      (node (ref "U402") (pin "1") (pinfunction "+VS_1") (pintype "power_in"))
      (node (ref "U403") (pin "1") (pinfunction "+VS_1") (pintype "power_in"))
    )
    (net (code "58") (name "VUSB") (class "Default")
      (node (ref "C104") (pin "1") (pinfunction "1_1") (pintype "passive"))
      (node (ref "JP101") (pin "VBUS1") (pinfunction "VCC_VBUS1") (pintype "bidirectional"))
      (node (ref "R106") (pin "2") (pinfunction "2_2") (pintype "passive"))
    )
    (net (code "59") (name "VUSB_") (class "Default")
      (node (ref "C101") (pin "1") (pinfunction "1_1") (pintype "passive"))
      (node (ref "C105") (pin "1") (pinfunction "1_1") (pintype "passive"))
      (node (ref "IC101") (pin "37") (pinfunction "VUSB_37") (pintype "bidirectional"))
    )
    (net (code "60") (name "WG1") (class "Default")
      (node (ref "K101") (pin "COM") (pinfunction "COM_COM") (pintype "passive"))
      (node (ref "TP15") (pin "1") (pinfunction "1_1") (pintype "passive"))
    )
    (net (code "61") (name "WG2") (class "Default")
      (node (ref "K101") (pin "NC") (pinfunction "NC_NC") (pintype "passive"))
      (node (ref "TP14") (pin "1") (pinfunction "1_1") (pintype "passive"))
    )
    (net (code "62") (name "_+12V") (class "Default")
      (node (ref "C201") (pin "+") (pinfunction "+_+") (pintype "passive"))
      (node (ref "F201") (pin "2") (pinfunction "2_2") (pintype "passive"))
      (node (ref "U303") (pin "3") (pinfunction "IP-_3") (pintype "passive"))
      (node (ref "U303") (pin "4") (pinfunction "IP-_4") (pintype "passive"))
    )
    (net (code "63") (name "_VCC") (class "Default")
      (node (ref "C203") (pin "+") (pinfunction "+_+") (pintype "passive"))
      (node (ref "F202") (pin "2") (pinfunction "2_2") (pintype "passive"))
      (node (ref "U301") (pin "3") (pinfunction "IP-_3") (pintype "passive"))
      (node (ref "U301") (pin "4") (pinfunction "IP-_4") (pintype "passive"))
    )
    (net (code "64") (name "unconnected-(D101-A-Pad3)") (class "Default")
      (node (ref "D101") (pin "3") (pinfunction "A_3") (pintype "passive"))
    )
    (net (code "65") (name "unconnected-(D103-A-Pad3)") (class "Default")
      (node (ref "D103") (pin "3") (pinfunction "A_3") (pintype "passive"))
    )
    (net (code "66") (name "unconnected-(IC101-NC{slash}ICCK{slash}ICPGC-Pad12)") (class "Default")
      (node (ref "IC101") (pin "12") (pinfunction "NC/ICCK/ICPGC_12") (pintype "bidirectional"))
    )
    (net (code "67") (name "unconnected-(IC101-NC{slash}ICDT{slash}ICPGD-Pad13)") (class "Default")
      (node (ref "IC101") (pin "13") (pinfunction "NC/ICDT/ICPGD_13") (pintype "bidirectional"))
    )
    (net (code "68") (name "unconnected-(IC101-NC{slash}ICPORTS-Pad34)") (class "Default")
      (node (ref "IC101") (pin "34") (pinfunction "NC/ICPORTS_34") (pintype "input"))
    )
    (net (code "69") (name "unconnected-(IC101-NC{slash}~{ICRST}{slash}IVVPP-Pad33)") (class "Default")
      (node (ref "IC101") (pin "33") (pinfunction "NC/~{ICRST}/IVVPP_33") (pintype "input"))
    )
    (net (code "70") (name "unconnected-(IC101-RB0{slash}AN12{slash}INT0{slash}LFT0{slash}SDI{slash}SDA-Pad8)") (class "Default")
      (node (ref "IC101") (pin "8") (pinfunction "RB0/AN12/INT0/LFT0/SDI/SDA_8") (pintype "bidirectional"))
    )
    (net (code "71") (name "unconnected-(IC101-RB1{slash}AN10{slash}INT1{slash}SCK{slash}SCL-Pad9)") (class "Default")
      (node (ref "IC101") (pin "9") (pinfunction "RB1/AN10/INT1/SCK/SCL_9") (pintype "bidirectional"))
    )
    (net (code "72") (name "unconnected-(IC101-RB2{slash}AN8{slash}INT2{slash}VMO-Pad10)") (class "Default")
      (node (ref "IC101") (pin "10") (pinfunction "RB2/AN8/INT2/VMO_10") (pintype "bidirectional"))
    )
    (net (code "73") (name "unconnected-(IC101-RB3{slash}AN9{slash}CCP2{slash}VPO-Pad11)") (class "Default")
      (node (ref "IC101") (pin "11") (pinfunction "RB3/AN9/CCP2/VPO_11") (pintype "bidirectional"))
    )
    (net (code "74") (name "unconnected-(IC101-RB4{slash}AN11{slash}KBI0{slash}CSSPP-Pad14)") (class "Default")
      (node (ref "IC101") (pin "14") (pinfunction "RB4/AN11/KBI0/CSSPP_14") (pintype "bidirectional"))
    )
    (net (code "75") (name "unconnected-(IC101-RB5{slash}KBI1{slash}PGM-Pad15)") (class "Default")
      (node (ref "IC101") (pin "15") (pinfunction "RB5/KBI1/PGM_15") (pintype "bidirectional"))
    )
    (net (code "76") (name "unconnected-(IC101-RC0{slash}TIOSO{slash}T13CKI-Pad32)") (class "Default")
      (node (ref "IC101") (pin "32") (pinfunction "RC0/TIOSO/T13CKI_32") (pintype "bidirectional"))
    )
    (net (code "77") (name "unconnected-(IC101-RC1{slash}T1OSI{slash}ICCP2{slash}~{UOE}-Pad35)") (class "Default")
      (node (ref "IC101") (pin "35") (pinfunction "RC1/T1OSI/ICCP2/~{UOE}_35") (pintype "bidirectional"))
    )
    (net (code "78") (name "unconnected-(IC101-RC6{slash}TX{slash}CK-Pad44)") (class "Default")
      (node (ref "IC101") (pin "44") (pinfunction "RC6/TX/CK_44") (pintype "bidirectional"))
    )
    (net (code "79") (name "unconnected-(IC101-RC7{slash}RX{slash}DT{slash}SDO-Pad1)") (class "Default")
      (node (ref "IC101") (pin "1") (pinfunction "RC7/RX/DT/SDO_1") (pintype "bidirectional"))
    )
    (net (code "80") (name "unconnected-(IC101-RD5{slash}SPP5{slash}P1B-Pad3)") (class "Default")
      (node (ref "IC101") (pin "3") (pinfunction "RD5/SPP5/P1B_3") (pintype "bidirectional"))
    )
    (net (code "81") (name "unconnected-(IC101-RD6{slash}SPP6{slash}P1C-Pad4)") (class "Default")
      (node (ref "IC101") (pin "4") (pinfunction "RD6/SPP6/P1C_4") (pintype "bidirectional"))
    )
    (net (code "82") (name "unconnected-(IC101-RD7{slash}SPP7{slash}P1D-Pad5)") (class "Default")
      (node (ref "IC101") (pin "5") (pinfunction "RD7/SPP7/P1D_5") (pintype "bidirectional"))
    )
    (net (code "83") (name "unconnected-(JP101-ID-PadID1)") (class "Default")
      (node (ref "JP101") (pin "ID1") (pinfunction "ID_ID1") (pintype "bidirectional"))
    )
    (net (code "84") (name "unconnected-(K101-PadNO)") (class "Default")
      (node (ref "K101") (pin "NO") (pinfunction "NO_NO") (pintype "passive"))
    )
  )
)
